# S3220B4.net
KiCad netlist of a schematic drawn in Altium Designer
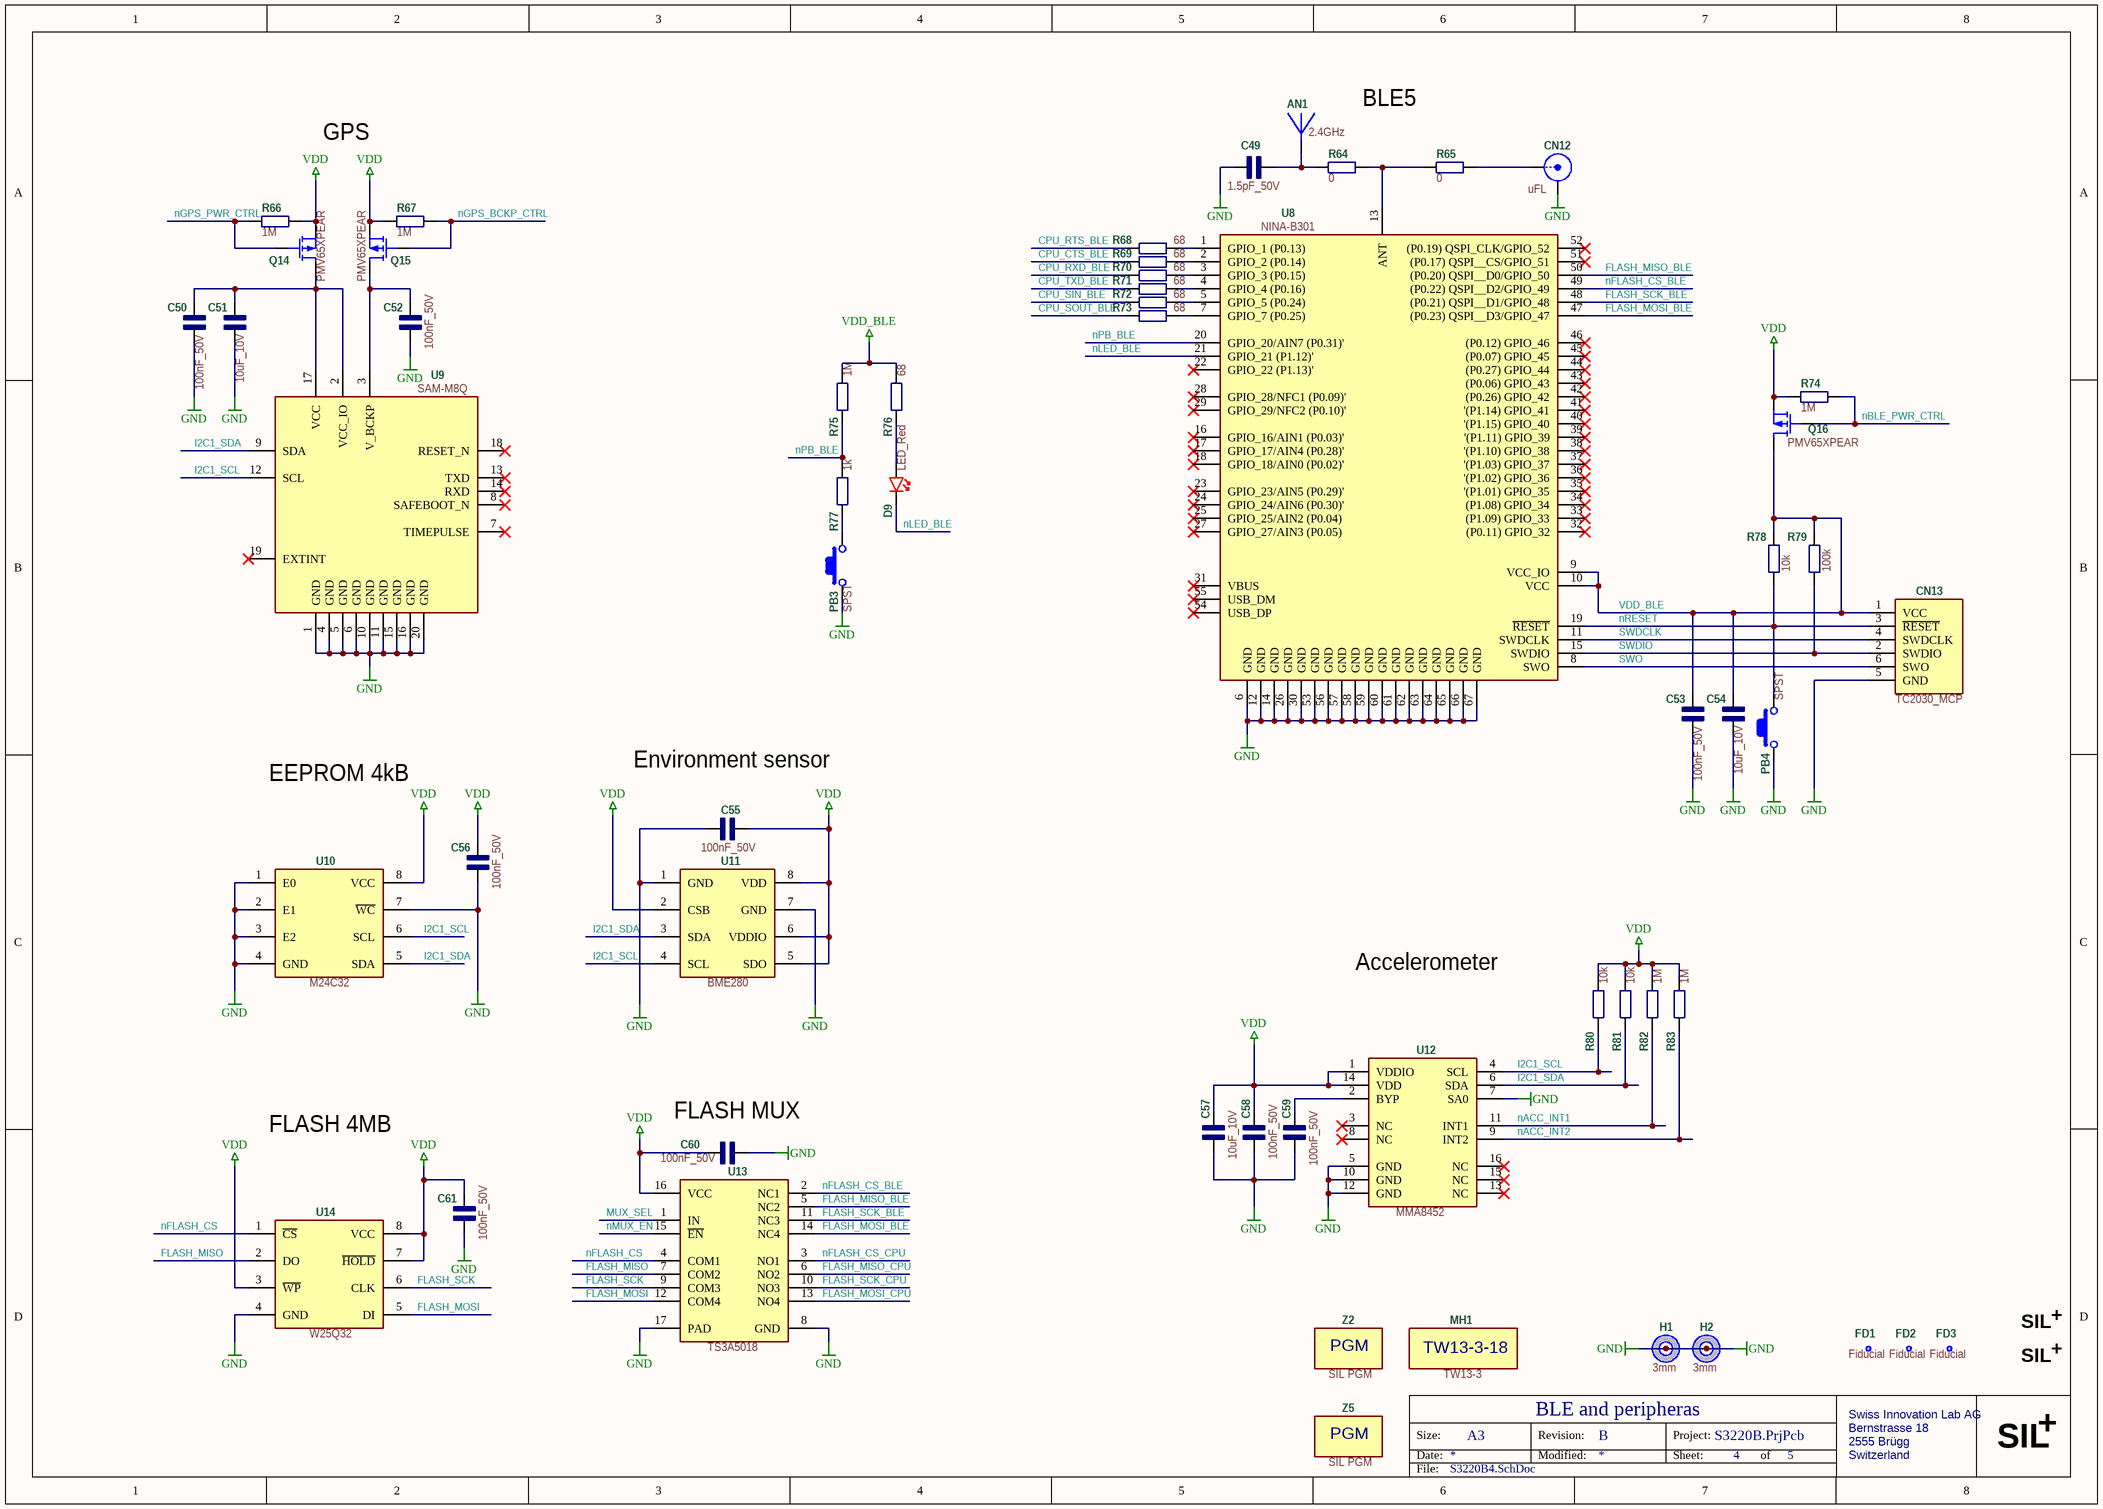
[diagram p0: S3220B4.SchDoc]

(export (version "E")
  (design (tool "Eeschema 10.0.6"))
  (components
    (comp (ref "AN1")
      (value "2.4GHz")
      (footprint "AN_2400-PCB-B")
      (description "2.4 GHz PCB antenna")
      (fields
        (field (name "MANUFACTURER") "Swiss Innovation Lab")
        (field (name "MANUFACTURER PART NUMBER") "SIL AN24GHZ")
      )
      (libsource (lib "SIL") (part "AN_2.4GHz-PCB"))
    )
    (comp (ref "C49")
      (value "1.5pF_50V")
      (footprint "SIL:C_0603")
      (description "1.5pF ±0.1pF 50V Ceramic Capacitor C0G, NP0 0603 (1608 Metric)")
      (fields
        (field (name "MANUFACTURER") "Samsung Electro-Mechanics")
        (field (name "MANUFACTURER PART NUMBER") "CL10C1R5BB8NNNC")
      )
      (libsource (lib "SIL") (part "C_1.5pF_50V"))
    )
    (comp (ref "C50")
      (value "100nF_50V")
      (footprint "SIL:C_0603")
      (description "0.1µF ±10% 50V Ceramic Capacitor X7R 0603 (1608 Metric)")
      (fields
        (field (name "MANUFACTURER") "TDK")
        (field (name "MANUFACTURER PART NUMBER") "C1608X7R1H104K080AA")
      )
      (libsource (lib "SIL") (part "C_100nF_50V"))
    )
    (comp (ref "C51")
      (value "10uF_10V")
      (footprint "SIL:C_0603")
      (description "10µF ±10% 10V Ceramic Capacitor X5R 0603 (1608 Metric)")
      (fields
        (field (name "MANUFACTURER") "Murata Electronics North America")
        (field (name "MANUFACTURER PART NUMBER") "GRM188R61A106KE69D")
      )
      (libsource (lib "SIL") (part "C_10uF_10V"))
    )
    (comp (ref "C52")
      (value "100nF_50V")
      (footprint "SIL:C_0603")
      (description "0.1µF ±10% 50V Ceramic Capacitor X7R 0603 (1608 Metric)")
      (fields
        (field (name "MANUFACTURER") "TDK")
        (field (name "MANUFACTURER PART NUMBER") "C1608X7R1H104K080AA")
      )
      (libsource (lib "SIL") (part "C_100nF_50V"))
    )
    (comp (ref "C53")
      (value "100nF_50V")
      (footprint "SIL:C_0603")
      (description "0.1µF ±10% 50V Ceramic Capacitor X7R 0603 (1608 Metric)")
      (fields
        (field (name "MANUFACTURER") "TDK")
        (field (name "MANUFACTURER PART NUMBER") "C1608X7R1H104K080AA")
      )
      (libsource (lib "SIL") (part "C_100nF_50V"))
    )
    (comp (ref "C54")
      (value "10uF_10V")
      (footprint "SIL:C_0603")
      (description "10µF ±10% 10V Ceramic Capacitor X5R 0603 (1608 Metric)")
      (fields
        (field (name "MANUFACTURER") "Murata Electronics North America")
        (field (name "MANUFACTURER PART NUMBER") "GRM188R61A106KE69D")
      )
      (libsource (lib "SIL") (part "C_10uF_10V"))
    )
    (comp (ref "C55")
      (value "100nF_50V")
      (footprint "SIL:C_0603")
      (description "0.1µF ±10% 50V Ceramic Capacitor X7R 0603 (1608 Metric)")
      (fields
        (field (name "MANUFACTURER") "TDK")
        (field (name "MANUFACTURER PART NUMBER") "C1608X7R1H104K080AA")
      )
      (libsource (lib "") (part "C_100nF_50V_3"))
    )
    (comp (ref "C56")
      (value "100nF_50V")
      (footprint "SIL:C_0603")
      (description "0.1µF ±10% 50V Ceramic Capacitor X7R 0603 (1608 Metric)")
      (fields
        (field (name "MANUFACTURER") "TDK")
        (field (name "MANUFACTURER PART NUMBER") "C1608X7R1H104K080AA")
      )
      (libsource (lib "SIL") (part "C_100nF_50V"))
    )
    (comp (ref "C57")
      (value "10uF_10V")
      (footprint "SIL:C_0603")
      (description "10µF ±10% 10V Ceramic Capacitor X5R 0603 (1608 Metric)")
      (fields
        (field (name "MANUFACTURER") "Murata Electronics North America")
        (field (name "MANUFACTURER PART NUMBER") "GRM188R61A106KE69D")
      )
      (libsource (lib "SIL") (part "C_10uF_10V"))
    )
    (comp (ref "C58")
      (value "100nF_50V")
      (footprint "SIL:C_0603")
      (description "0.1µF ±10% 50V Ceramic Capacitor X7R 0603 (1608 Metric)")
      (fields
        (field (name "MANUFACTURER") "TDK")
        (field (name "MANUFACTURER PART NUMBER") "C1608X7R1H104K080AA")
      )
      (libsource (lib "") (part "C_100nF_50V_2"))
    )
    (comp (ref "C59")
      (value "100nF_50V")
      (footprint "SIL:C_0603")
      (description "0.1µF ±10% 50V Ceramic Capacitor X7R 0603 (1608 Metric)")
      (fields
        (field (name "MANUFACTURER") "TDK")
        (field (name "MANUFACTURER PART NUMBER") "C1608X7R1H104K080AA")
      )
      (libsource (lib "") (part "C_100nF_50V_2"))
    )
    (comp (ref "C60")
      (value "100nF_50V")
      (footprint "SIL:C_0603")
      (description "0.1µF ±10% 50V Ceramic Capacitor X7R 0603 (1608 Metric)")
      (fields
        (field (name "MANUFACTURER") "TDK")
        (field (name "MANUFACTURER PART NUMBER") "C1608X7R1H104K080AA")
      )
      (libsource (lib "") (part "C_100nF_50V_1"))
    )
    (comp (ref "C61")
      (value "100nF_50V")
      (footprint "SIL:C_0603")
      (description "0.1µF ±10% 50V Ceramic Capacitor X7R 0603 (1608 Metric)")
      (fields
        (field (name "MANUFACTURER") "TDK")
        (field (name "MANUFACTURER PART NUMBER") "C1608X7R1H104K080AA")
      )
      (libsource (lib "SIL") (part "C_100nF_50V"))
    )
    (comp (ref "CN12")
      (value "uFL")
      (footprint "CN_RF_uFL")
      (description "Ultra Miniature Coaxial Connector Jack, Male Pin 50 Ohm Surface Mount Solder")
      (fields
        (field (name "MANUFACTURER") "TE Connectivity AMP Connectors")
        (field (name "MANUFACTURER PART NUMBER") "1909763-1")
      )
      (libsource (lib "SIL") (part "CN_RF_uFL"))
    )
    (comp (ref "CN13")
      (value "TC2030_MCP")
      (footprint "SIL:CN_TC2030-MCP-NL")
      (description "TC2030-MCP-NL")
      (libsource (lib "SIL") (part "CN_TC2030"))
    )
    (comp (ref "D9")
      (value "LED_Red")
      (footprint "LED_0603")
      (description "Red 631nm LED Indication - Discrete 2V 0603")
      (fields
        (field (name "MANUFACTURER") "Lite-On Inc.")
        (field (name "MANUFACTURER PART NUMBER") "LTST-C193KRKT-5A")
      )
      (libsource (lib "SIL") (part "D_LED_R_5mA"))
    )
    (comp (ref "FD1")
      (value "Fiducial")
      (footprint "FD_Fiducial")
      (description "Reference point for assembly machine")
      (fields (field (name "MANUFACTURER") "Swiss Innovation Lab"))
      (libsource (lib "SIL") (part "FD_Fiducial"))
    )
    (comp (ref "FD2")
      (value "Fiducial")
      (footprint "FD_Fiducial")
      (description "Reference point for assembly machine")
      (fields (field (name "MANUFACTURER") "Swiss Innovation Lab"))
      (libsource (lib "SIL") (part "FD_Fiducial"))
    )
    (comp (ref "FD3")
      (value "Fiducial")
      (footprint "FD_Fiducial")
      (description "Reference point for assembly machine")
      (fields (field (name "MANUFACTURER") "Swiss Innovation Lab"))
      (libsource (lib "SIL") (part "FD_Fiducial"))
    )
    (comp (ref "H1")
      (value "3mm")
      (footprint "H_Hole_30M_55M")
      (description "Hole 3mm, Pad 5.5mm")
      (fields
        (field (name "MANUFACTURER") "Swiss Innovation Lab")
        (field (name "MANUFACTURER PART NUMBER") "Hole 3mm")
      )
      (libsource (lib "SIL") (part "H_Hole_3M_55M"))
    )
    (comp (ref "H2")
      (value "3mm")
      (footprint "H_Hole_30M_55M")
      (description "Hole 3mm, Pad 5.5mm")
      (fields
        (field (name "MANUFACTURER") "Swiss Innovation Lab")
        (field (name "MANUFACTURER PART NUMBER") "Hole 3mm")
      )
      (libsource (lib "SIL") (part "H_Hole_3M_55M"))
    )
    (comp (ref "MH1")
      (value "TW13-3")
      (footprint "MH_TW13-3")
      (description "Case Takachi TW13-3")
      (fields (field (name "MANUFACTURER") "Takachi"))
      (libsource (lib "SIL") (part "MH_TW13-3"))
    )
    (comp (ref "PB3")
      (value "SPST")
      (footprint "SIL:PB_PTS810")
      (description "Tactile Switch SPST-NO Top Actuated Surface Mount")
      (fields
        (field (name "MANUFACTURER") "C&K")
        (field (name "MANUFACTURER PART NUMBER") "PTS810 SJM 250 SMTR LFS")
      )
      (libsource (lib "SIL") (part "PB_SPST_2.5mm"))
    )
    (comp (ref "PB4")
      (value "SPST")
      (footprint "SIL:PB_PTS810")
      (description "Tactile Switch SPST-NO Top Actuated Surface Mount")
      (fields
        (field (name "MANUFACTURER") "C&K")
        (field (name "MANUFACTURER PART NUMBER") "PTS810 SJM 250 SMTR LFS")
      )
      (libsource (lib "SIL") (part "PB_SPST_2.5mm"))
    )
    (comp (ref "Q14")
      (value "PMV65XPEAR")
      (footprint "U_SOT23-3")
      (description "P-Channel 20V 2.8A (Ta) 480mW (Ta), 6.25W (Tc) Surface Mount TO-236AB (SOT23)")
      (fields (field (name "MANUFACTURER") "Nexperia USA Inc."))
      (libsource (lib "SIL") (part "Q_PMV65"))
    )
    (comp (ref "Q15")
      (value "PMV65XPEAR")
      (footprint "U_SOT23-3")
      (description "P-Channel 20V 2.8A (Ta) 480mW (Ta), 6.25W (Tc) Surface Mount TO-236AB (SOT23)")
      (fields (field (name "MANUFACTURER") "Nexperia USA Inc."))
      (libsource (lib "SIL") (part "Q_PMV65"))
    )
    (comp (ref "Q16")
      (value "PMV65XPEAR")
      (footprint "U_SOT23-3")
      (description "P-Channel 20V 2.8A (Ta) 480mW (Ta), 6.25W (Tc) Surface Mount TO-236AB (SOT23)")
      (fields (field (name "MANUFACTURER") "Nexperia USA Inc."))
      (libsource (lib "SIL") (part "Q_PMV65"))
    )
    (comp (ref "R64")
      (value "0")
      (footprint "SIL:R_0603")
      (description "0 Ohms Jumper 0.1W, 1/10W Chip Resistor 0603 (1608 Metric) Automotive AEC-Q200 Thick Film")
      (fields
        (field (name "MANUFACTURER") "Panasonic Electronic Components")
        (field (name "MANUFACTURER PART NUMBER") "ERJ-3GEY0R00V")
      )
      (libsource (lib "SIL") (part "R_0_1%"))
    )
    (comp (ref "R65")
      (value "0")
      (footprint "SIL:R_0603")
      (description "0 Ohms Jumper 0.1W, 1/10W Chip Resistor 0603 (1608 Metric) Automotive AEC-Q200 Thick Film")
      (fields
        (field (name "MANUFACTURER") "Panasonic Electronic Components")
        (field (name "MANUFACTURER PART NUMBER") "ERJ-3GEY0R00V")
      )
      (libsource (lib "SIL") (part "R_0_1%"))
    )
    (comp (ref "R66")
      (value "1M")
      (footprint "SIL:R_0603")
      (description "1 MOhms ±1% 0.1W, 1/10W Chip Resistor 0603 (1608 Metric) Automotive AEC-Q200 Thick Film")
      (fields
        (field (name "MANUFACTURER") "Panasonic Electronic Components")
        (field (name "MANUFACTURER PART NUMBER") "ERJ-3EKF1004V")
      )
      (libsource (lib "") (part "R_1M_1%_2"))
    )
    (comp (ref "R67")
      (value "1M")
      (footprint "SIL:R_0603")
      (description "1 MOhms ±1% 0.1W, 1/10W Chip Resistor 0603 (1608 Metric) Automotive AEC-Q200 Thick Film")
      (fields
        (field (name "MANUFACTURER") "Panasonic Electronic Components")
        (field (name "MANUFACTURER PART NUMBER") "ERJ-3EKF1004V")
      )
      (libsource (lib "") (part "R_1M_1%_1"))
    )
    (comp (ref "R68")
      (value "68")
      (footprint "SIL:R_0603")
      (description "68 Ohms ±1% 0.1W, 1/10W Chip Resistor 0603 (1608 Metric) Automotive AEC-Q200 Thick Film")
      (fields
        (field (name "MANUFACTURER") "Panasonic Electronic Components")
        (field (name "MANUFACTURER PART NUMBER") "ERJ-3EKF68R0V")
      )
      (libsource (lib "SIL") (part "R_68_1%"))
    )
    (comp (ref "R69")
      (value "68")
      (footprint "SIL:R_0603")
      (description "68 Ohms ±1% 0.1W, 1/10W Chip Resistor 0603 (1608 Metric) Automotive AEC-Q200 Thick Film")
      (fields
        (field (name "MANUFACTURER") "Panasonic Electronic Components")
        (field (name "MANUFACTURER PART NUMBER") "ERJ-3EKF68R0V")
      )
      (libsource (lib "SIL") (part "R_68_1%"))
    )
    (comp (ref "R70")
      (value "68")
      (footprint "SIL:R_0603")
      (description "68 Ohms ±1% 0.1W, 1/10W Chip Resistor 0603 (1608 Metric) Automotive AEC-Q200 Thick Film")
      (fields
        (field (name "MANUFACTURER") "Panasonic Electronic Components")
        (field (name "MANUFACTURER PART NUMBER") "ERJ-3EKF68R0V")
      )
      (libsource (lib "SIL") (part "R_68_1%"))
    )
    (comp (ref "R71")
      (value "68")
      (footprint "SIL:R_0603")
      (description "68 Ohms ±1% 0.1W, 1/10W Chip Resistor 0603 (1608 Metric) Automotive AEC-Q200 Thick Film")
      (fields
        (field (name "MANUFACTURER") "Panasonic Electronic Components")
        (field (name "MANUFACTURER PART NUMBER") "ERJ-3EKF68R0V")
      )
      (libsource (lib "SIL") (part "R_68_1%"))
    )
    (comp (ref "R72")
      (value "68")
      (footprint "SIL:R_0603")
      (description "68 Ohms ±1% 0.1W, 1/10W Chip Resistor 0603 (1608 Metric) Automotive AEC-Q200 Thick Film")
      (fields
        (field (name "MANUFACTURER") "Panasonic Electronic Components")
        (field (name "MANUFACTURER PART NUMBER") "ERJ-3EKF68R0V")
      )
      (libsource (lib "SIL") (part "R_68_1%"))
    )
    (comp (ref "R73")
      (value "68")
      (footprint "SIL:R_0603")
      (description "68 Ohms ±1% 0.1W, 1/10W Chip Resistor 0603 (1608 Metric) Automotive AEC-Q200 Thick Film")
      (fields
        (field (name "MANUFACTURER") "Panasonic Electronic Components")
        (field (name "MANUFACTURER PART NUMBER") "ERJ-3EKF68R0V")
      )
      (libsource (lib "SIL") (part "R_68_1%"))
    )
    (comp (ref "R74")
      (value "1M")
      (footprint "SIL:R_0603")
      (description "1 MOhms ±1% 0.1W, 1/10W Chip Resistor 0603 (1608 Metric) Automotive AEC-Q200 Thick Film")
      (fields
        (field (name "MANUFACTURER") "Panasonic Electronic Components")
        (field (name "MANUFACTURER PART NUMBER") "ERJ-3EKF1004V")
      )
      (libsource (lib "") (part "R_1M_1%_1"))
    )
    (comp (ref "R75")
      (value "1M")
      (footprint "SIL:R_0603")
      (description "1 MOhms ±1% 0.1W, 1/10W Chip Resistor 0603 (1608 Metric) Automotive AEC-Q200 Thick Film")
      (fields
        (field (name "MANUFACTURER") "Panasonic Electronic Components")
        (field (name "MANUFACTURER PART NUMBER") "ERJ-3EKF1004V")
      )
      (libsource (lib "SIL") (part "R_1M_1%"))
    )
    (comp (ref "R76")
      (value "68")
      (footprint "SIL:R_0603")
      (description "68 Ohms ±1% 0.1W, 1/10W Chip Resistor 0603 (1608 Metric) Automotive AEC-Q200 Thick Film")
      (fields
        (field (name "MANUFACTURER") "Panasonic Electronic Components")
        (field (name "MANUFACTURER PART NUMBER") "ERJ-3EKF68R0V")
      )
      (libsource (lib "") (part "R_68_1%_1"))
    )
    (comp (ref "R77")
      (value "1k")
      (footprint "SIL:R_0603")
      (description "1 kOhms ±1% 0.1W, 1/10W Chip Resistor 0603 (1608 Metric) Automotive AEC-Q200 Thick Film")
      (fields
        (field (name "MANUFACTURER") "Panasonic Electronic Components")
        (field (name "MANUFACTURER PART NUMBER") "ERJ-3EKF1001V")
      )
      (libsource (lib "SIL") (part "R_1k_1%"))
    )
    (comp (ref "R78")
      (value "10k")
      (footprint "SIL:R_0603")
      (description "10 kOhms ±1% 0.1W, 1/10W Chip Resistor 0603 (1608 Metric) Automotive AEC-Q200 Thick Film")
      (fields
        (field (name "MANUFACTURER") "Panasonic Electronic Components")
        (field (name "MANUFACTURER PART NUMBER") "ERJ-3EKF1002V")
      )
      (libsource (lib "SIL") (part "R_10k_1%"))
    )
    (comp (ref "R79")
      (value "100k")
      (footprint "SIL:R_0603")
      (description "100 kOhms ±1% 0.1W, 1/10W Chip Resistor 0603 (1608 Metric) Automotive AEC-Q200 Thick Film")
      (fields
        (field (name "MANUFACTURER") "Panasonic Electronic Components")
        (field (name "MANUFACTURER PART NUMBER") "ERJ-3EKF1003V")
      )
      (libsource (lib "SIL") (part "R_100k_1%"))
    )
    (comp (ref "R80")
      (value "10k")
      (footprint "SIL:R_0603")
      (description "10 kOhms ±1% 0.1W, 1/10W Chip Resistor 0603 (1608 Metric) Automotive AEC-Q200 Thick Film")
      (fields
        (field (name "MANUFACTURER") "Panasonic Electronic Components")
        (field (name "MANUFACTURER PART NUMBER") "ERJ-3EKF1002V")
      )
      (libsource (lib "SIL") (part "R_10k_1%"))
    )
    (comp (ref "R81")
      (value "10k")
      (footprint "SIL:R_0603")
      (description "10 kOhms ±1% 0.1W, 1/10W Chip Resistor 0603 (1608 Metric) Automotive AEC-Q200 Thick Film")
      (fields
        (field (name "MANUFACTURER") "Panasonic Electronic Components")
        (field (name "MANUFACTURER PART NUMBER") "ERJ-3EKF1002V")
      )
      (libsource (lib "SIL") (part "R_10k_1%"))
    )
    (comp (ref "R82")
      (value "1M")
      (footprint "SIL:R_0603")
      (description "1 MOhms ±1% 0.1W, 1/10W Chip Resistor 0603 (1608 Metric) Automotive AEC-Q200 Thick Film")
      (fields
        (field (name "MANUFACTURER") "Panasonic Electronic Components")
        (field (name "MANUFACTURER PART NUMBER") "ERJ-3EKF1004V")
      )
      (libsource (lib "SIL") (part "R_1M_1%"))
    )
    (comp (ref "R83")
      (value "1M")
      (footprint "SIL:R_0603")
      (description "1 MOhms ±1% 0.1W, 1/10W Chip Resistor 0603 (1608 Metric) Automotive AEC-Q200 Thick Film")
      (fields
        (field (name "MANUFACTURER") "Panasonic Electronic Components")
        (field (name "MANUFACTURER PART NUMBER") "ERJ-3EKF1004V")
      )
      (libsource (lib "SIL") (part "R_1M_1%"))
    )
    (comp (ref "U8")
      (value "NINA-B301")
      (footprint "U_NINA-B301")
      (description "MOD BLE 4.2 NORDIC NRF52840 SOC")
      (fields (field (name "MANUFACTURER") "uBlox"))
      (libsource (lib "SIL") (part "U_NINA-B301"))
    )
    (comp (ref "U9")
      (value "SAM-M8Q")
      (footprint "U_SAM-M8Q")
      (description "SAM-M8Q RF Receiver Galileo, GLONASS, GPS 1.575GHz, 1.602GHz -165dBm 400kbps")
      (fields
        (field (name "MANUFACTURER") "U-Blox America Inc.")
        (field (name "MANUFACTURER PART NUMBER") "SAM-M8Q-0-10")
      )
      (libsource (lib "SIL") (part "U_SAM-M8Q"))
    )
    (comp (ref "U10")
      (value "M24C32")
      (footprint "U_8-SOIC_3.9")
      (description "EEPROM Memory IC 32Kb (4K x 8) I2C 1MHz 450ns 8-SO")
      (fields
        (field (name "MANUFACTURER") "STMicroelectronics")
        (field (name "MANUFACTURER PART NUMBER") "M24C32-WMN6TP")
      )
      (libsource (lib "SIL") (part "U_M24C32"))
    )
    (comp (ref "U11")
      (value "BME280")
      (footprint "SIL:U_BME280")
      (description "Humidity Temperature Sensor 0 ~ 100% RH I2C, SPI ±3% 1s Surface Mount")
      (fields (field (name "MANUFACTURER") "Bosch Sensortec"))
      (libsource (lib "SIL") (part "U_BME280"))
    )
    (comp (ref "U12")
      (value "MMA8452")
      (footprint "U_16-QFN-5X3")
      (description "Accelerometer X, Y, Z Axis ±2g, 4g, 8g 0.78Hz ~ 400Hz 16-QFN (3x3)")
      (fields
        (field (name "MANUFACTURER") "NXP USA Inc.")
        (field (name "MANUFACTURER PART NUMBER") "MMA8452QT")
      )
      (libsource (lib "SIL") (part "U_MMA8452"))
    )
    (comp (ref "U13")
      (value "TS3A5018")
      (footprint "U_16-VFQFN")
      (description "4 Circuit IC Switch 2:1 10Ohm 16-UQFN (2.6x1.8)")
      (fields
        (field (name "MANUFACTURER") "Texas Instruments")
        (field (name "MANUFACTURER PART NUMBER") "TS3A5018RGYR")
      )
      (libsource (lib "SIL") (part "U_TS3A5018"))
    )
    (comp (ref "U14")
      (value "W25Q32")
      (footprint "U_8-SOIC_5.3")
      (description "FLASH - NOR Memory IC 32Mb (4M x 8) SPI - Quad I/O 133MHz  8-SOIC")
      (fields
        (field (name "MANUFACTURER") "Winbond Electronics")
        (field (name "MANUFACTURER PART NUMBER") "W25Q32JVSSIQ")
      )
      (libsource (lib "SIL") (part "U_W25Q32"))
    )
    (comp (ref "Z2")
      (value "SIL PGM")
      (footprint "Z_SIL-PGM")
      (description "Programmer Template")
      (fields (field (name "MANUFACTURER") "Swiss Innovation Lab"))
      (libsource (lib "SIL") (part "Z_PGM"))
    )
    (comp (ref "Z3")
      (value "SIL logo")
      (footprint "Z_SIL-logo")
      (fields
        (field (name "MANUFACTURER") "Swiss Innovation Lab")
        (field (name "MANUFACTURER PART NUMBER") "SIL Logo")
      )
      (libsource (lib "SIL") (part "Z_SIL_logo"))
    )
    (comp (ref "Z4")
      (value "SIL logo")
      (footprint "Z_SIL-logo")
      (fields
        (field (name "MANUFACTURER") "Swiss Innovation Lab")
        (field (name "MANUFACTURER PART NUMBER") "SIL Logo")
      )
      (libsource (lib "SIL") (part "Z_SIL_logo"))
    )
    (comp (ref "Z5")
      (value "SIL PGM")
      (footprint "Z_SIL-PGM")
      (description "Programmer Template")
      (fields (field (name "MANUFACTURER") "Swiss Innovation Lab"))
      (libsource (lib "SIL") (part "Z_PGM"))
    )
  )
  (nets
    (net (code "1") (name "/CPU_CTS_BLE") (class "Default")
      (node (ref "R69") (pin "1") (pinfunction "1_1") (pintype "passive"))
    )
    (net (code "2") (name "/CPU_RTS_BLE") (class "Default")
      (node (ref "R68") (pin "1") (pinfunction "1_1") (pintype "passive"))
    )
    (net (code "3") (name "/CPU_RXD_BLE") (class "Default")
      (node (ref "R70") (pin "1") (pinfunction "1_1") (pintype "passive"))
    )
    (net (code "4") (name "/CPU_SIN_BLE") (class "Default")
      (node (ref "R72") (pin "1") (pinfunction "1_1") (pintype "passive"))
    )
    (net (code "5") (name "/CPU_SOUT_BLE") (class "Default")
      (node (ref "R73") (pin "1") (pinfunction "1_1") (pintype "passive"))
    )
    (net (code "6") (name "/CPU_TXD_BLE") (class "Default")
      (node (ref "R71") (pin "1") (pinfunction "1_1") (pintype "passive"))
    )
    (net (code "7") (name "/FLASH_MISO") (class "Default")
      (node (ref "U13") (pin "7") (pinfunction "COM2_7") (pintype "passive"))
      (node (ref "U14") (pin "2") (pinfunction "DO_2") (pintype "passive"))
    )
    (net (code "8") (name "/FLASH_MISO_BLE") (class "Default")
      (node (ref "U13") (pin "5") (pinfunction "NC2_5") (pintype "passive"))
      (node (ref "U8") (pin "50") (pinfunction "(P0.20)_QSPI__D0/GPIO_50_50") (pintype "passive"))
    )
    (net (code "9") (name "/FLASH_MISO_CPU") (class "Default")
      (node (ref "U13") (pin "6") (pinfunction "NO2_6") (pintype "passive"))
    )
    (net (code "10") (name "/FLASH_MOSI") (class "Default")
      (node (ref "U13") (pin "12") (pinfunction "COM4_12") (pintype "passive"))
      (node (ref "U14") (pin "5") (pinfunction "DI_5") (pintype "passive"))
    )
    (net (code "11") (name "/FLASH_MOSI_BLE") (class "Default")
      (node (ref "U13") (pin "14") (pinfunction "NC4_14") (pintype "passive"))
      (node (ref "U8") (pin "47") (pinfunction "(P0.23)_QSPI__D3/GPIO_47_47") (pintype "passive"))
    )
    (net (code "12") (name "/FLASH_MOSI_CPU") (class "Default")
      (node (ref "U13") (pin "13") (pinfunction "NO4_13") (pintype "passive"))
    )
    (net (code "13") (name "/FLASH_SCK") (class "Default")
      (node (ref "U13") (pin "9") (pinfunction "COM3_9") (pintype "passive"))
      (node (ref "U14") (pin "6") (pinfunction "CLK_6") (pintype "passive"))
    )
    (net (code "14") (name "/FLASH_SCK_BLE") (class "Default")
      (node (ref "U13") (pin "11") (pinfunction "NC3_11") (pintype "passive"))
      (node (ref "U8") (pin "48") (pinfunction "(P0.21)_QSPI__D1/GPIO_48_48") (pintype "passive"))
    )
    (net (code "15") (name "/FLASH_SCK_CPU") (class "Default")
      (node (ref "U13") (pin "10") (pinfunction "NO3_10") (pintype "passive"))
    )
    (net (code "16") (name "/I2C1_SCL") (class "Default")
      (node (ref "R80") (pin "1") (pinfunction "1_1") (pintype "passive"))
      (node (ref "U10") (pin "6") (pinfunction "SCL_6") (pintype "passive"))
      (node (ref "U11") (pin "4") (pinfunction "SCL_4") (pintype "passive"))
      (node (ref "U12") (pin "4") (pinfunction "SCL_4") (pintype "passive"))
      (node (ref "U9") (pin "12") (pinfunction "SCL_12") (pintype "passive"))
    )
    (net (code "17") (name "/I2C1_SDA") (class "Default")
      (node (ref "R81") (pin "1") (pinfunction "1_1") (pintype "passive"))
      (node (ref "U10") (pin "5") (pinfunction "SDA_5") (pintype "passive"))
      (node (ref "U11") (pin "3") (pinfunction "SDA_3") (pintype "passive"))
      (node (ref "U12") (pin "6") (pinfunction "SDA_6") (pintype "passive"))
      (node (ref "U9") (pin "9") (pinfunction "SDA_9") (pintype "passive"))
    )
    (net (code "18") (name "/MUX_SEL") (class "Default")
      (node (ref "U13") (pin "1") (pinfunction "IN_1") (pintype "passive"))
    )
    (net (code "19") (name "/SWDCLK") (class "Default")
      (node (ref "CN13") (pin "4") (pinfunction "SWDCLK_4") (pintype "passive"))
      (node (ref "U8") (pin "11") (pinfunction "SWDCLK_11") (pintype "passive"))
    )
    (net (code "20") (name "/SWDIO") (class "Default")
      (node (ref "CN13") (pin "2") (pinfunction "SWDIO_2") (pintype "passive"))
      (node (ref "R79") (pin "1") (pinfunction "1_1") (pintype "passive"))
      (node (ref "U8") (pin "15") (pinfunction "SWDIO_15") (pintype "passive"))
    )
    (net (code "21") (name "/SWO") (class "Default")
      (node (ref "CN13") (pin "6") (pinfunction "SWO_6") (pintype "passive"))
      (node (ref "U8") (pin "8") (pinfunction "SWO_8") (pintype "passive"))
    )
    (net (code "22") (name "/nACC_INT1") (class "Default")
      (node (ref "R82") (pin "2") (pinfunction "2_2") (pintype "passive"))
      (node (ref "U12") (pin "11") (pinfunction "INT1_11") (pintype "passive"))
    )
    (net (code "23") (name "/nACC_INT2") (class "Default")
      (node (ref "R83") (pin "2") (pinfunction "2_2") (pintype "passive"))
      (node (ref "U12") (pin "9") (pinfunction "INT2_9") (pintype "passive"))
    )
    (net (code "24") (name "/nBLE_PWR_CTRL") (class "Default")
      (node (ref "Q16") (pin "1") (pinfunction "G_1") (pintype "passive"))
      (node (ref "R74") (pin "1") (pinfunction "1_1") (pintype "passive"))
    )
    (net (code "25") (name "/nFLASH_CS") (class "Default")
      (node (ref "U13") (pin "4") (pinfunction "COM1_4") (pintype "passive"))
      (node (ref "U14") (pin "1") (pinfunction "~{CS}_1") (pintype "passive"))
    )
    (net (code "26") (name "/nFLASH_CS_BLE") (class "Default")
      (node (ref "U13") (pin "2") (pinfunction "NC1_2") (pintype "passive"))
      (node (ref "U8") (pin "49") (pinfunction "(P0.22)_QSPI__D2/GPIO_49_49") (pintype "passive"))
    )
    (net (code "27") (name "/nFLASH_CS_CPU") (class "Default")
      (node (ref "U13") (pin "3") (pinfunction "NO1_3") (pintype "passive"))
    )
    (net (code "28") (name "/nGPS_BCKP_CTRL") (class "Default")
      (node (ref "Q15") (pin "1") (pinfunction "G_1") (pintype "passive"))
      (node (ref "R67") (pin "1") (pinfunction "1_1") (pintype "passive"))
    )
    (net (code "29") (name "/nGPS_PWR_CTRL") (class "Default")
      (node (ref "Q14") (pin "1") (pinfunction "G_1") (pintype "passive"))
      (node (ref "R66") (pin "1") (pinfunction "1_1") (pintype "passive"))
    )
    (net (code "30") (name "/nLED_BLE") (class "Default")
      (node (ref "D9") (pin "2") (pinfunction "K_2") (pintype "passive"))
      (node (ref "U8") (pin "21") (pinfunction "GPIO_21_(P1.12)'_21") (pintype "passive"))
    )
    (net (code "31") (name "/nMUX_EN") (class "Default")
      (node (ref "U13") (pin "15") (pinfunction "~{EN}_15") (pintype "passive"))
    )
    (net (code "32") (name "/nPB_BLE") (class "Default")
      (node (ref "R75") (pin "2") (pinfunction "2_2") (pintype "passive"))
      (node (ref "R77") (pin "2") (pinfunction "2_2") (pintype "passive"))
      (node (ref "U8") (pin "20") (pinfunction "GPIO_20/AIN7_(P0.31)'_20") (pintype "passive"))
    )
    (net (code "33") (name "/nRESET") (class "Default")
      (node (ref "CN13") (pin "3") (pinfunction "~{RESET}_3") (pintype "passive"))
      (node (ref "PB4") (pin "2") (pinfunction "2_2") (pintype "passive"))
      (node (ref "R78") (pin "1") (pinfunction "1_1") (pintype "passive"))
      (node (ref "U8") (pin "19") (pinfunction "~{RESET}_19") (pintype "passive"))
    )
    (net (code "34") (name "GND") (class "Default")
      (node (ref "C49") (pin "1") (pintype "passive"))
      (node (ref "C50") (pin "1") (pintype "passive"))
      (node (ref "C51") (pin "1") (pintype "passive"))
      (node (ref "C52") (pin "1") (pintype "passive"))
      (node (ref "C53") (pin "1") (pintype "passive"))
      (node (ref "C54") (pin "1") (pintype "passive"))
      (node (ref "C55") (pin "2") (pintype "passive"))
      (node (ref "C56") (pin "1") (pintype "passive"))
      (node (ref "C57") (pin "1") (pintype "passive"))
      (node (ref "C58") (pin "2") (pintype "passive"))
      (node (ref "C59") (pin "2") (pintype "passive"))
      (node (ref "C60") (pin "2") (pintype "passive"))
      (node (ref "C61") (pin "1") (pintype "passive"))
      (node (ref "CN12") (pin "G") (pinfunction "G_G") (pintype "passive"))
      (node (ref "CN13") (pin "5") (pinfunction "GND_5") (pintype "passive"))
      (node (ref "H1") (pin "0") (pinfunction "0_0") (pintype "passive"))
      (node (ref "H2") (pin "0") (pinfunction "0_0") (pintype "passive"))
      (node (ref "PB3") (pin "2") (pinfunction "2_2") (pintype "passive"))
      (node (ref "PB4") (pin "1") (pinfunction "1_1") (pintype "passive"))
      (node (ref "U10") (pin "1") (pinfunction "E0_1") (pintype "passive"))
      (node (ref "U10") (pin "2") (pinfunction "E1_2") (pintype "passive"))
      (node (ref "U10") (pin "3") (pinfunction "E2_3") (pintype "passive"))
      (node (ref "U10") (pin "4") (pinfunction "GND_4") (pintype "power_in"))
      (node (ref "U10") (pin "7") (pinfunction "~{WC}_7") (pintype "passive"))
      (node (ref "U11") (pin "1") (pinfunction "GND_1") (pintype "power_in"))
      (node (ref "U11") (pin "7") (pinfunction "GND_7") (pintype "power_in"))
      (node (ref "U12") (pin "10") (pinfunction "GND_10") (pintype "power_in"))
      (node (ref "U12") (pin "12") (pinfunction "GND_12") (pintype "power_in"))
      (node (ref "U12") (pin "5") (pinfunction "GND_5") (pintype "power_in"))
      (node (ref "U12") (pin "7") (pinfunction "SA0_7") (pintype "passive"))
      (node (ref "U13") (pin "17") (pinfunction "PAD_17") (pintype "power_in"))
      (node (ref "U13") (pin "8") (pinfunction "GND_8") (pintype "power_in"))
      (node (ref "U14") (pin "4") (pinfunction "GND_4") (pintype "power_in"))
      (node (ref "U8") (pin "12") (pinfunction "GND_12") (pintype "power_in"))
      (node (ref "U8") (pin "14") (pinfunction "GND_14") (pintype "power_in"))
      (node (ref "U8") (pin "26") (pinfunction "GND_26") (pintype "power_in"))
      (node (ref "U8") (pin "30") (pinfunction "GND_30") (pintype "power_in"))
      (node (ref "U8") (pin "53") (pinfunction "GND_53") (pintype "power_in"))
      (node (ref "U8") (pin "56") (pinfunction "GND_56") (pintype "power_in"))
      (node (ref "U8") (pin "57") (pinfunction "GND_57") (pintype "passive"))
      (node (ref "U8") (pin "58") (pinfunction "GND_58") (pintype "power_in"))
      (node (ref "U8") (pin "59") (pinfunction "GND_59") (pintype "power_in"))
      (node (ref "U8") (pin "6") (pinfunction "GND_6") (pintype "power_in"))
      (node (ref "U8") (pin "60") (pinfunction "GND_60") (pintype "power_in"))
      (node (ref "U8") (pin "61") (pinfunction "GND_61") (pintype "power_in"))
      (node (ref "U8") (pin "62") (pinfunction "GND_62") (pintype "power_in"))
      (node (ref "U8") (pin "63") (pinfunction "GND_63") (pintype "power_in"))
      (node (ref "U8") (pin "64") (pinfunction "GND_64") (pintype "power_in"))
      (node (ref "U8") (pin "65") (pinfunction "GND_65") (pintype "power_in"))
      (node (ref "U8") (pin "66") (pinfunction "GND_66") (pintype "power_in"))
      (node (ref "U8") (pin "67") (pinfunction "GND_67") (pintype "power_in"))
      (node (ref "U9") (pin "1") (pinfunction "GND_1") (pintype "passive"))
      (node (ref "U9") (pin "10") (pinfunction "GND_10") (pintype "passive"))
      (node (ref "U9") (pin "11") (pinfunction "GND_11") (pintype "passive"))
      (node (ref "U9") (pin "15") (pinfunction "GND_15") (pintype "passive"))
      (node (ref "U9") (pin "16") (pinfunction "GND_16") (pintype "passive"))
      (node (ref "U9") (pin "20") (pinfunction "GND_20") (pintype "passive"))
      (node (ref "U9") (pin "4") (pinfunction "GND_4") (pintype "passive"))
      (node (ref "U9") (pin "5") (pinfunction "GND_5") (pintype "passive"))
      (node (ref "U9") (pin "6") (pinfunction "GND_6") (pintype "passive"))
    )
    (net (code "35") (name "Net-(AN1-Pad1)") (class "Default")
      (node (ref "AN1") (pin "1") (pintype "passive"))
      (node (ref "C49") (pin "2") (pintype "passive"))
      (node (ref "R64") (pin "1") (pinfunction "1_1") (pintype "passive"))
    )
    (net (code "36") (name "Net-(CN12-PadS)") (class "Default")
      (node (ref "CN12") (pin "S") (pinfunction "S_S") (pintype "passive"))
      (node (ref "R65") (pin "2") (pinfunction "2_2") (pintype "passive"))
    )
    (net (code "37") (name "Net-(D9-A)") (class "Default")
      (node (ref "D9") (pin "1") (pinfunction "A_1") (pintype "passive"))
      (node (ref "R76") (pin "1") (pinfunction "1_1") (pintype "passive"))
    )
    (net (code "38") (name "Net-(PB3-Pad1)") (class "Default")
      (node (ref "PB3") (pin "1") (pinfunction "1_1") (pintype "passive"))
      (node (ref "R77") (pin "1") (pinfunction "1_1") (pintype "passive"))
    )
    (net (code "39") (name "Net-(Q14-D)") (class "Default")
      (node (ref "C50") (pin "2") (pintype "passive"))
      (node (ref "C51") (pin "2") (pintype "passive"))
      (node (ref "Q14") (pin "3") (pinfunction "D_3") (pintype "passive"))
      (node (ref "U9") (pin "17") (pinfunction "VCC_17") (pintype "passive"))
      (node (ref "U9") (pin "2") (pinfunction "VCC_IO_2") (pintype "passive"))
    )
    (net (code "40") (name "Net-(Q15-D)") (class "Default")
      (node (ref "C52") (pin "2") (pintype "passive"))
      (node (ref "Q15") (pin "3") (pinfunction "D_3") (pintype "passive"))
      (node (ref "U9") (pin "3") (pinfunction "V_BCKP_3") (pintype "passive"))
    )
    (net (code "41") (name "Net-(U8-ANT)") (class "Default")
      (node (ref "R64") (pin "2") (pinfunction "2_2") (pintype "passive"))
      (node (ref "R65") (pin "1") (pinfunction "1_1") (pintype "passive"))
      (node (ref "U8") (pin "13") (pinfunction "ANT_13") (pintype "passive"))
    )
    (net (code "42") (name "Net-(U8-GPIO_1_(P0.13))") (class "Default")
      (node (ref "R68") (pin "2") (pinfunction "2_2") (pintype "passive"))
      (node (ref "U8") (pin "1") (pinfunction "GPIO_1_(P0.13)_1") (pintype "passive"))
    )
    (net (code "43") (name "Net-(U8-GPIO_2_(P0.14))") (class "Default")
      (node (ref "R69") (pin "2") (pinfunction "2_2") (pintype "passive"))
      (node (ref "U8") (pin "2") (pinfunction "GPIO_2_(P0.14)_2") (pintype "passive"))
    )
    (net (code "44") (name "Net-(U8-GPIO_3_(P0.15))") (class "Default")
      (node (ref "R70") (pin "2") (pinfunction "2_2") (pintype "passive"))
      (node (ref "U8") (pin "3") (pinfunction "GPIO_3_(P0.15)_3") (pintype "passive"))
    )
    (net (code "45") (name "Net-(U8-GPIO_4_(P0.16))") (class "Default")
      (node (ref "R71") (pin "2") (pinfunction "2_2") (pintype "passive"))
      (node (ref "U8") (pin "4") (pinfunction "GPIO_4_(P0.16)_4") (pintype "passive"))
    )
    (net (code "46") (name "Net-(U8-GPIO_5_(P0.24))") (class "Default")
      (node (ref "R72") (pin "2") (pinfunction "2_2") (pintype "passive"))
      (node (ref "U8") (pin "5") (pinfunction "GPIO_5_(P0.24)_5") (pintype "passive"))
    )
    (net (code "47") (name "Net-(U8-GPIO_7_(P0.25))") (class "Default")
      (node (ref "R73") (pin "2") (pinfunction "2_2") (pintype "passive"))
      (node (ref "U8") (pin "7") (pinfunction "GPIO_7_(P0.25)_7") (pintype "passive"))
    )
    (net (code "48") (name "Net-(U12-BYP)") (class "Default")
      (node (ref "C59") (pin "1") (pintype "passive"))
      (node (ref "U12") (pin "2") (pinfunction "BYP_2") (pintype "passive"))
    )
    (net (code "49") (name "VDD") (class "Default")
      (node (ref "C55") (pin "1") (pintype "passive"))
      (node (ref "C56") (pin "2") (pintype "passive"))
      (node (ref "C57") (pin "2") (pintype "passive"))
      (node (ref "C58") (pin "1") (pintype "passive"))
      (node (ref "C60") (pin "1") (pintype "passive"))
      (node (ref "C61") (pin "2") (pintype "passive"))
      (node (ref "Q14") (pin "2") (pinfunction "S_2") (pintype "passive"))
      (node (ref "Q15") (pin "2") (pinfunction "S_2") (pintype "passive"))
      (node (ref "Q16") (pin "2") (pinfunction "S_2") (pintype "passive"))
      (node (ref "R66") (pin "2") (pinfunction "2_2") (pintype "passive"))
      (node (ref "R67") (pin "2") (pinfunction "2_2") (pintype "passive"))
      (node (ref "R74") (pin "2") (pinfunction "2_2") (pintype "passive"))
      (node (ref "R80") (pin "2") (pinfunction "2_2") (pintype "passive"))
      (node (ref "R81") (pin "2") (pinfunction "2_2") (pintype "passive"))
      (node (ref "R82") (pin "1") (pinfunction "1_1") (pintype "passive"))
      (node (ref "R83") (pin "1") (pinfunction "1_1") (pintype "passive"))
      (node (ref "U10") (pin "8") (pinfunction "VCC_8") (pintype "power_in"))
      (node (ref "U11") (pin "2") (pinfunction "CSB_2") (pintype "passive"))
      (node (ref "U11") (pin "5") (pinfunction "SDO_5") (pintype "passive"))
      (node (ref "U11") (pin "6") (pinfunction "VDDIO_6") (pintype "power_in"))
      (node (ref "U11") (pin "8") (pinfunction "VDD_8") (pintype "power_in"))
      (node (ref "U12") (pin "1") (pinfunction "VDDIO_1") (pintype "power_in"))
      (node (ref "U12") (pin "14") (pinfunction "VDD_14") (pintype "power_in"))
      (node (ref "U13") (pin "16") (pinfunction "VCC_16") (pintype "power_in"))
      (node (ref "U14") (pin "3") (pinfunction "~{WP}_3") (pintype "passive"))
      (node (ref "U14") (pin "7") (pinfunction "~{HOLD}_7") (pintype "passive"))
      (node (ref "U14") (pin "8") (pinfunction "VCC_8") (pintype "power_in"))
    )
    (net (code "50") (name "VDD_BLE") (class "Default")
      (node (ref "C53") (pin "2") (pintype "passive"))
      (node (ref "C54") (pin "2") (pintype "passive"))
      (node (ref "CN13") (pin "1") (pinfunction "VCC_1") (pintype "power_in"))
      (node (ref "Q16") (pin "3") (pinfunction "D_3") (pintype "passive"))
      (node (ref "R75") (pin "1") (pinfunction "1_1") (pintype "passive"))
      (node (ref "R76") (pin "2") (pinfunction "2_2") (pintype "passive"))
      (node (ref "R78") (pin "2") (pinfunction "2_2") (pintype "passive"))
      (node (ref "R79") (pin "2") (pinfunction "2_2") (pintype "passive"))
      (node (ref "U8") (pin "10") (pinfunction "VCC_10") (pintype "power_in"))
      (node (ref "U8") (pin "9") (pinfunction "VCC_IO_9") (pintype "power_in"))
    )
    (net (code "51") (name "unconnected-(FD1-Pad0)") (class "Default")
      (node (ref "FD1") (pin "0") (pinfunction "0_0") (pintype "passive"))
    )
    (net (code "52") (name "unconnected-(FD2-Pad0)") (class "Default")
      (node (ref "FD2") (pin "0") (pinfunction "0_0") (pintype "passive"))
    )
    (net (code "53") (name "unconnected-(FD3-Pad0)") (class "Default")
      (node (ref "FD3") (pin "0") (pinfunction "0_0") (pintype "passive"))
    )
    (net (code "54") (name "unconnected-(MH1-Pad0)") (class "Default")
      (node (ref "MH1") (pin "0") (pinfunction "0_0") (pintype "passive"))
    )
    (net (code "55") (name "unconnected-(U8-'(P1.01)_GPIO_35-Pad35)") (class "Default")
      (node (ref "U8") (pin "35") (pinfunction "'(P1.01)_GPIO_35_35") (pintype "passive+no_connect"))
    )
    (net (code "56") (name "unconnected-(U8-'(P1.02)_GPIO_36-Pad36)") (class "Default")
      (node (ref "U8") (pin "36") (pinfunction "'(P1.02)_GPIO_36_36") (pintype "passive+no_connect"))
    )
    (net (code "57") (name "unconnected-(U8-'(P1.03)_GPIO_37-Pad37)") (class "Default")
      (node (ref "U8") (pin "37") (pinfunction "'(P1.03)_GPIO_37_37") (pintype "passive+no_connect"))
    )
    (net (code "58") (name "unconnected-(U8-'(P1.10)_GPIO_38-Pad38)") (class "Default")
      (node (ref "U8") (pin "38") (pinfunction "'(P1.10)_GPIO_38_38") (pintype "passive+no_connect"))
    )
    (net (code "59") (name "unconnected-(U8-'(P1.11)_GPIO_39-Pad39)") (class "Default")
      (node (ref "U8") (pin "39") (pinfunction "'(P1.11)_GPIO_39_39") (pintype "passive+no_connect"))
    )
    (net (code "60") (name "unconnected-(U8-'(P1.14)_GPIO_41-Pad41)") (class "Default")
      (node (ref "U8") (pin "41") (pinfunction "'(P1.14)_GPIO_41_41") (pintype "passive+no_connect"))
    )
    (net (code "61") (name "unconnected-(U8-'(P1.15)_GPIO_40-Pad40)") (class "Default")
      (node (ref "U8") (pin "40") (pinfunction "'(P1.15)_GPIO_40_40") (pintype "passive+no_connect"))
    )
    (net (code "62") (name "unconnected-(U8-(P0.06)_GPIO_43-Pad43)") (class "Default")
      (node (ref "U8") (pin "43") (pinfunction "(P0.06)_GPIO_43_43") (pintype "passive+no_connect"))
    )
    (net (code "63") (name "unconnected-(U8-(P0.07)_GPIO_45-Pad45)") (class "Default")
      (node (ref "U8") (pin "45") (pinfunction "(P0.07)_GPIO_45_45") (pintype "passive+no_connect"))
    )
    (net (code "64") (name "unconnected-(U8-(P0.11)_GPIO_32-Pad32)") (class "Default")
      (node (ref "U8") (pin "32") (pinfunction "(P0.11)_GPIO_32_32") (pintype "passive+no_connect"))
    )
    (net (code "65") (name "unconnected-(U8-(P0.12)_GPIO_46-Pad46)") (class "Default")
      (node (ref "U8") (pin "46") (pinfunction "(P0.12)_GPIO_46_46") (pintype "passive+no_connect"))
    )
    (net (code "66") (name "unconnected-(U8-(P0.17)_QSPI__CS{slash}GPIO_51-Pad51)") (class "Default")
      (node (ref "U8") (pin "51") (pinfunction "(P0.17)_QSPI__CS/GPIO_51_51") (pintype "passive+no_connect"))
    )
    (net (code "67") (name "unconnected-(U8-(P0.19)_QSPI_CLK{slash}GPIO_52-Pad52)") (class "Default")
      (node (ref "U8") (pin "52") (pinfunction "(P0.19)_QSPI_CLK/GPIO_52_52") (pintype "passive+no_connect"))
    )
    (net (code "68") (name "unconnected-(U8-(P0.26)_GPIO_42-Pad42)") (class "Default")
      (node (ref "U8") (pin "42") (pinfunction "(P0.26)_GPIO_42_42") (pintype "passive+no_connect"))
    )
    (net (code "69") (name "unconnected-(U8-(P0.27)_GPIO_44-Pad44)") (class "Default")
      (node (ref "U8") (pin "44") (pinfunction "(P0.27)_GPIO_44_44") (pintype "passive+no_connect"))
    )
    (net (code "70") (name "unconnected-(U8-(P1.08)_GPIO_34-Pad34)") (class "Default")
      (node (ref "U8") (pin "34") (pinfunction "(P1.08)_GPIO_34_34") (pintype "passive+no_connect"))
    )
    (net (code "71") (name "unconnected-(U8-(P1.09)_GPIO_33-Pad33)") (class "Default")
      (node (ref "U8") (pin "33") (pinfunction "(P1.09)_GPIO_33_33") (pintype "passive+no_connect"))
    )
    (net (code "72") (name "unconnected-(U8-GPIO_16{slash}AIN1_(P0.03)'-Pad16)") (class "Default")
      (node (ref "U8") (pin "16") (pinfunction "GPIO_16/AIN1_(P0.03)'_16") (pintype "passive+no_connect"))
    )
    (net (code "73") (name "unconnected-(U8-GPIO_17{slash}AIN4_(P0.28)'-Pad17)") (class "Default")
      (node (ref "U8") (pin "17") (pinfunction "GPIO_17/AIN4_(P0.28)'_17") (pintype "passive+no_connect"))
    )
    (net (code "74") (name "unconnected-(U8-GPIO_18{slash}AIN0_(P0.02)'-Pad18)") (class "Default")
      (node (ref "U8") (pin "18") (pinfunction "GPIO_18/AIN0_(P0.02)'_18") (pintype "passive+no_connect"))
    )
    (net (code "75") (name "unconnected-(U8-GPIO_22_(P1.13)'-Pad22)") (class "Default")
      (node (ref "U8") (pin "22") (pinfunction "GPIO_22_(P1.13)'_22") (pintype "passive+no_connect"))
    )
    (net (code "76") (name "unconnected-(U8-GPIO_23{slash}AIN5_(P0.29)'-Pad23)") (class "Default")
      (node (ref "U8") (pin "23") (pinfunction "GPIO_23/AIN5_(P0.29)'_23") (pintype "passive+no_connect"))
    )
    (net (code "77") (name "unconnected-(U8-GPIO_24{slash}AIN6_(P0.30)'-Pad24)") (class "Default")
      (node (ref "U8") (pin "24") (pinfunction "GPIO_24/AIN6_(P0.30)'_24") (pintype "passive+no_connect"))
    )
    (net (code "78") (name "unconnected-(U8-GPIO_25{slash}AIN2_(P0.04)-Pad25)") (class "Default")
      (node (ref "U8") (pin "25") (pinfunction "GPIO_25/AIN2_(P0.04)_25") (pintype "passive+no_connect"))
    )
    (net (code "79") (name "unconnected-(U8-GPIO_27{slash}AIN3_(P0.05)-Pad27)") (class "Default")
      (node (ref "U8") (pin "27") (pinfunction "GPIO_27/AIN3_(P0.05)_27") (pintype "passive+no_connect"))
    )
    (net (code "80") (name "unconnected-(U8-GPIO_28{slash}NFC1_(P0.09)'-Pad28)") (class "Default")
      (node (ref "U8") (pin "28") (pinfunction "GPIO_28/NFC1_(P0.09)'_28") (pintype "passive+no_connect"))
    )
    (net (code "81") (name "unconnected-(U8-GPIO_29{slash}NFC2_(P0.10)'-Pad29)") (class "Default")
      (node (ref "U8") (pin "29") (pinfunction "GPIO_29/NFC2_(P0.10)'_29") (pintype "passive+no_connect"))
    )
    (net (code "82") (name "unconnected-(U8-USB_DM-Pad55)") (class "Default")
      (node (ref "U8") (pin "55") (pinfunction "USB_DM_55") (pintype "passive+no_connect"))
    )
    (net (code "83") (name "unconnected-(U8-USB_DP-Pad54)") (class "Default")
      (node (ref "U8") (pin "54") (pinfunction "USB_DP_54") (pintype "passive+no_connect"))
    )
    (net (code "84") (name "unconnected-(U8-VBUS-Pad31)") (class "Default")
      (node (ref "U8") (pin "31") (pinfunction "VBUS_31") (pintype "passive+no_connect"))
    )
    (net (code "85") (name "unconnected-(U9-EXTINT-Pad19)") (class "Default")
      (node (ref "U9") (pin "19") (pinfunction "EXTINT_19") (pintype "passive+no_connect"))
    )
    (net (code "86") (name "unconnected-(U9-RESET_N-Pad18)") (class "Default")
      (node (ref "U9") (pin "18") (pinfunction "RESET_N_18") (pintype "passive+no_connect"))
    )
    (net (code "87") (name "unconnected-(U9-RXD-Pad14)") (class "Default")
      (node (ref "U9") (pin "14") (pinfunction "RXD_14") (pintype "passive+no_connect"))
    )
    (net (code "88") (name "unconnected-(U9-SAFEBOOT_N-Pad8)") (class "Default")
      (node (ref "U9") (pin "8") (pinfunction "SAFEBOOT_N_8") (pintype "passive+no_connect"))
    )
    (net (code "89") (name "unconnected-(U9-TIMEPULSE-Pad7)") (class "Default")
      (node (ref "U9") (pin "7") (pinfunction "TIMEPULSE_7") (pintype "passive+no_connect"))
    )
    (net (code "90") (name "unconnected-(U9-TXD-Pad13)") (class "Default")
      (node (ref "U9") (pin "13") (pinfunction "TXD_13") (pintype "passive+no_connect"))
    )
    (net (code "91") (name "unconnected-(U12-NC-Pad3)") (class "Default")
      (node (ref "U12") (pin "3") (pinfunction "NC_3") (pintype "passive+no_connect"))
    )
    (net (code "92") (name "unconnected-(U12-NC-Pad8)") (class "Default")
      (node (ref "U12") (pin "8") (pinfunction "NC_8") (pintype "passive+no_connect"))
    )
    (net (code "93") (name "unconnected-(U12-NC-Pad13)") (class "Default")
      (node (ref "U12") (pin "13") (pinfunction "NC_13") (pintype "passive+no_connect"))
    )
    (net (code "94") (name "unconnected-(U12-NC-Pad15)") (class "Default")
      (node (ref "U12") (pin "15") (pinfunction "NC_15") (pintype "passive+no_connect"))
    )
    (net (code "95") (name "unconnected-(U12-NC-Pad16)") (class "Default")
      (node (ref "U12") (pin "16") (pinfunction "NC_16") (pintype "passive+no_connect"))
    )
    (net (code "96") (name "unconnected-(Z2-Pad0)") (class "Default")
      (node (ref "Z2") (pin "0") (pinfunction "0_0") (pintype "passive"))
    )
    (net (code "97") (name "unconnected-(Z3-Pad0)") (class "Default")
      (node (ref "Z3") (pin "0") (pinfunction "0_0") (pintype "passive"))
    )
    (net (code "98") (name "unconnected-(Z4-Pad0)") (class "Default")
      (node (ref "Z4") (pin "0") (pinfunction "0_0") (pintype "passive"))
    )
    (net (code "99") (name "unconnected-(Z5-Pad0)") (class "Default")
      (node (ref "Z5") (pin "0") (pinfunction "0_0") (pintype "passive"))
    )
  )
)
